# BikeNavigation.net
KiCad netlist of a schematic drawn in EAGLE
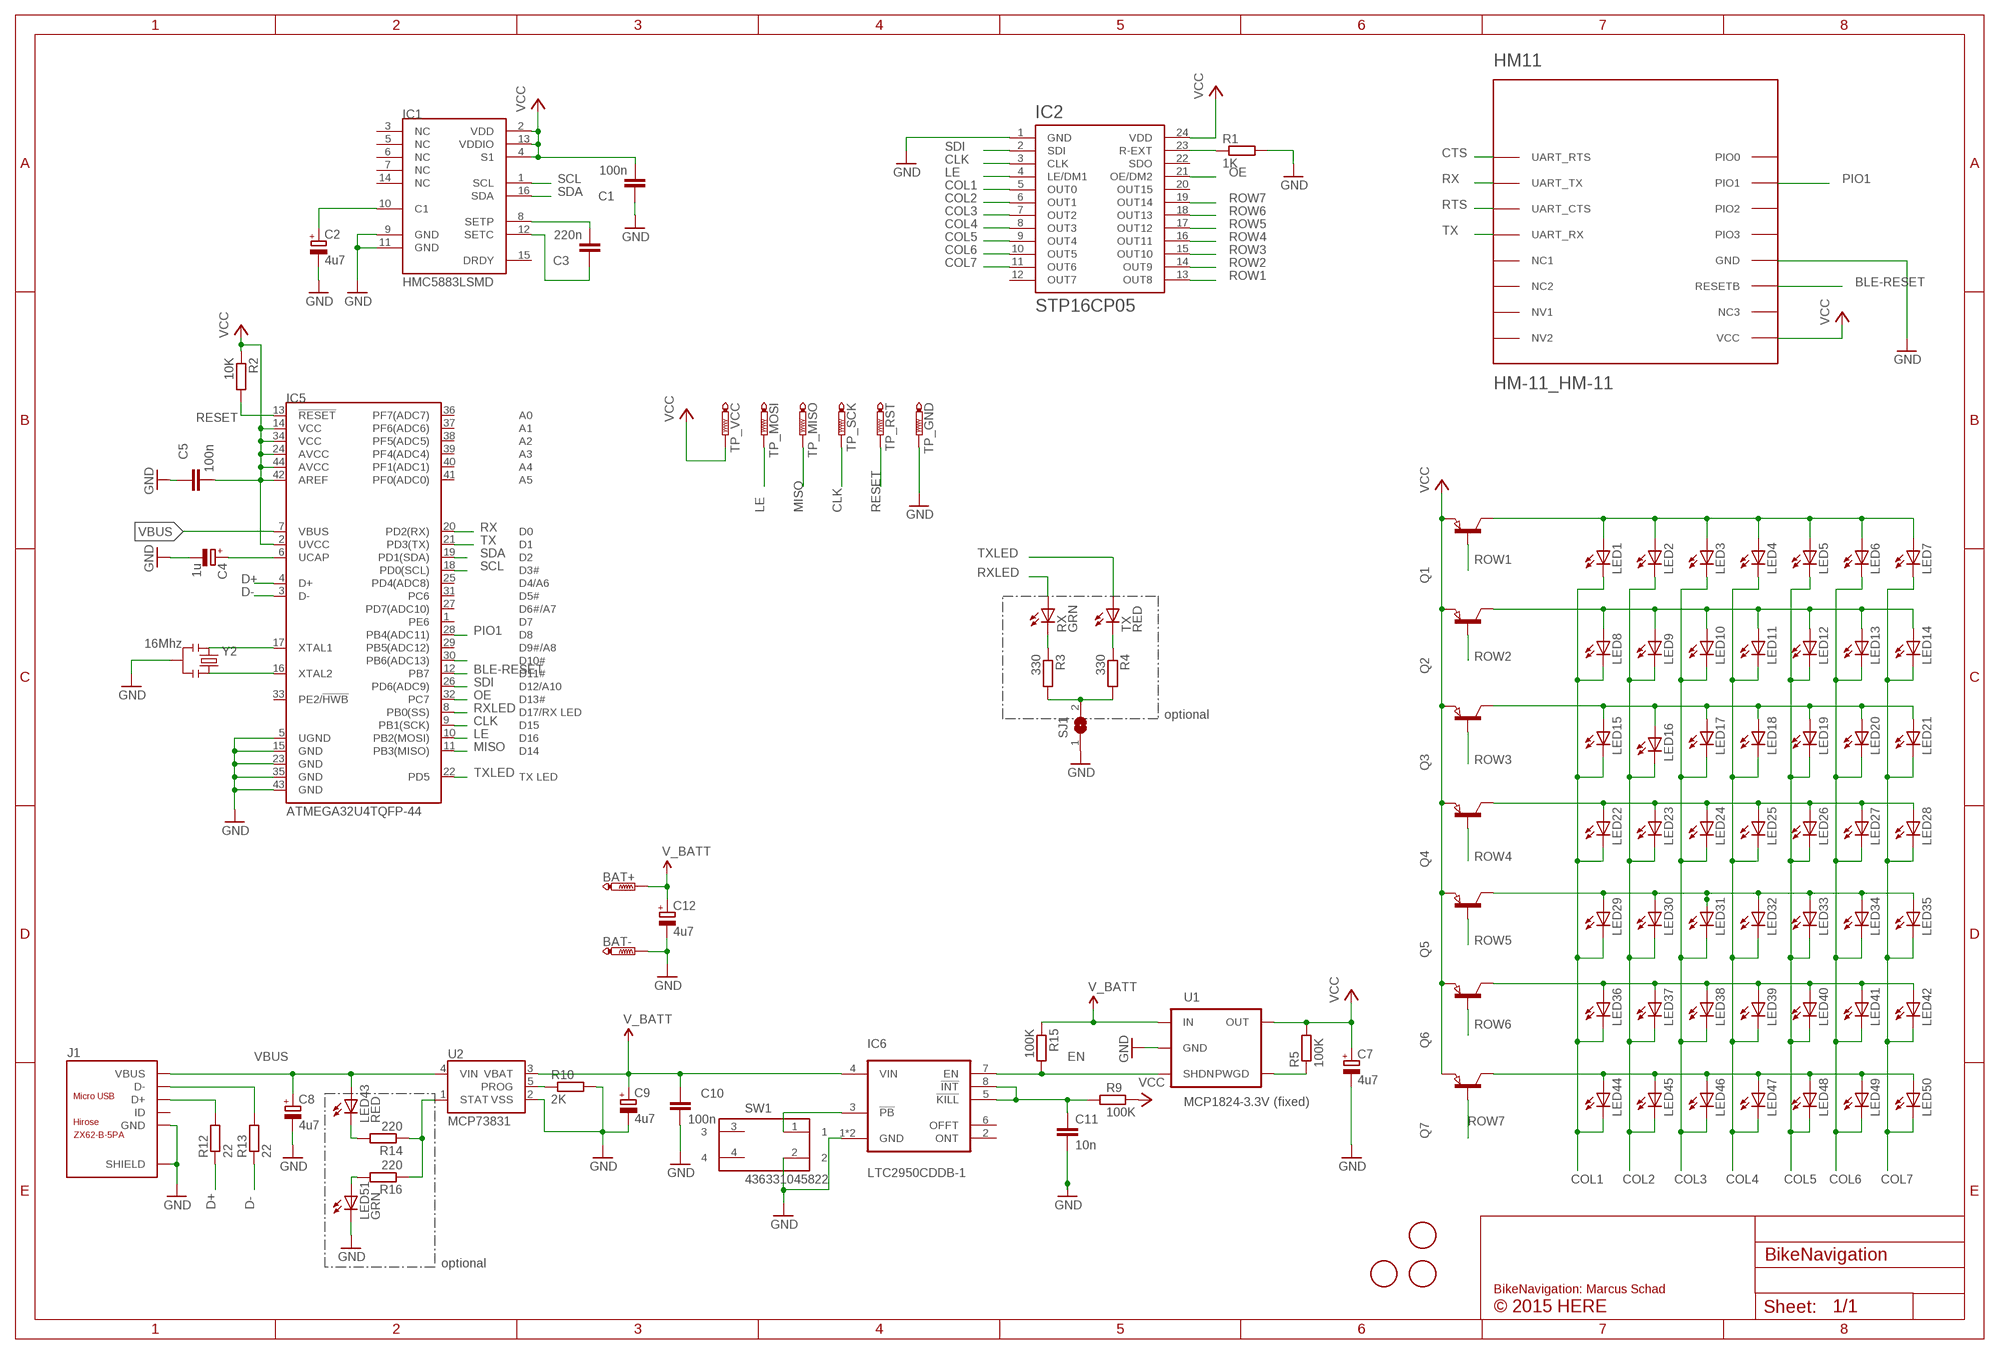
[diagram p0: schematic, sheet 1]

(export (version "E")
  (design (tool "Eeschema 10.0.6"))
  (components
    (comp (ref "BAT+")
      (value "PTR1TP20SQ")
      (footprint "eagle-import:TP20SQ")
      (libsource (lib "eagle-import") (part "PTR1TP20SQ"))
    )
    (comp (ref "BAT-")
      (value "PTR1TP20SQ")
      (footprint "eagle-import:TP20SQ")
      (libsource (lib "eagle-import") (part "PTR1TP20SQ"))
    )
    (comp (ref "C1")
      (value "100n")
      (footprint "eagle-import:C0402")
      (fields (field (name "PARTNO") "445-3445-1-ND"))
      (libsource (lib "eagle-import") (part "C-EUC0402"))
    )
    (comp (ref "C2")
      (value "4u7")
      (footprint "eagle-import:SMC_A")
      (libsource (lib "eagle-import") (part "CPOL-EUSMCA"))
    )
    (comp (ref "C3")
      (value "220n")
      (footprint "eagle-import:C0402")
      (fields (field (name "PARTNO") "445-3445-1-ND"))
      (libsource (lib "eagle-import") (part "C-EUC0402"))
    )
    (comp (ref "C4")
      (value "1u")
      (footprint "eagle-import:SMC_A")
      (libsource (lib "eagle-import") (part "CPOL-EUSMCA"))
    )
    (comp (ref "C5")
      (value "100n")
      (footprint "eagle-import:C0402")
      (fields (field (name "PARTNO") "445-3445-1-ND"))
      (libsource (lib "eagle-import") (part "C-EUC0402"))
    )
    (comp (ref "C7")
      (value "4u7")
      (footprint "eagle-import:SMC_A")
      (libsource (lib "eagle-import") (part "CPOL-EUSMCA"))
    )
    (comp (ref "C8")
      (value "4u7")
      (footprint "eagle-import:SMC_A")
      (libsource (lib "eagle-import") (part "CPOL-EUSMCA"))
    )
    (comp (ref "C9")
      (value "4u7")
      (footprint "eagle-import:SMC_A")
      (libsource (lib "eagle-import") (part "CPOL-EUSMCA"))
    )
    (comp (ref "C10")
      (value "100n")
      (footprint "eagle-import:C0402")
      (fields (field (name "PARTNO") "445-3445-1-ND"))
      (libsource (lib "eagle-import") (part "C-EUC0402"))
    )
    (comp (ref "C11")
      (value "10n")
      (footprint "eagle-import:C0402")
      (fields (field (name "PARTNO") "445-1260-1-ND"))
      (libsource (lib "eagle-import") (part "C-EUC0402"))
    )
    (comp (ref "C12")
      (value "4u7")
      (footprint "eagle-import:SMC_A")
      (libsource (lib "eagle-import") (part "CPOL-EUSMCA"))
    )
    (comp (ref "HM11")
      (value "HM-11_HM-11")
      (footprint "eagle-import:HM-11_HM-11")
      (libsource (lib "eagle-import") (part "HM-11_HM-11"))
    )
    (comp (ref "IC1")
      (value "HMC5883LSMD")
      (footprint "eagle-import:16LPCC")
      (libsource (lib "eagle-import") (part "HMC5883LSMD"))
    )
    (comp (ref "IC2")
      (value "STP16CP05")
      (footprint "eagle-import:TSSOP24")
      (libsource (lib "eagle-import") (part "STP16CP05"))
    )
    (comp (ref "IC5")
      (value "ATMEGA32U4TQFP-44")
      (footprint "eagle-import:TQFP44")
      (libsource (lib "eagle-import") (part "ATMEGA32U4TQFP-44"))
    )
    (comp (ref "IC6")
      (value "LTC2950CDDB-1")
      (footprint "eagle-import:DDB-8")
      (fields (field (name "PARTNO") "LTC2950IDDB-1#TRMPBFCT-ND"))
      (libsource (lib "eagle-import") (part "LTC2950-1DFN(3X2)"))
    )
    (comp (ref "J1")
      (value "MICRO-USB-SMD(ZX62-B-5PA)")
      (footprint "eagle-import:MICRO-USB5+6P-SMD-0.65-AB")
      (libsource (lib "eagle-import") (part "MICRO-USB-SMD(ZX62-B-5PA)"))
    )
    (comp (ref "LED1")
      (value "LEDCHIP-LED0603")
      (footprint "eagle-import:CHIP-LED0603")
      (libsource (lib "eagle-import") (part "LEDCHIP-LED0603"))
    )
    (comp (ref "LED2")
      (value "LEDCHIP-LED0603")
      (footprint "eagle-import:CHIP-LED0603")
      (libsource (lib "eagle-import") (part "LEDCHIP-LED0603"))
    )
    (comp (ref "LED3")
      (value "LEDCHIP-LED0603")
      (footprint "eagle-import:CHIP-LED0603")
      (libsource (lib "eagle-import") (part "LEDCHIP-LED0603"))
    )
    (comp (ref "LED4")
      (value "LEDCHIP-LED0603")
      (footprint "eagle-import:CHIP-LED0603")
      (libsource (lib "eagle-import") (part "LEDCHIP-LED0603"))
    )
    (comp (ref "LED5")
      (value "LEDCHIP-LED0603")
      (footprint "eagle-import:CHIP-LED0603")
      (libsource (lib "eagle-import") (part "LEDCHIP-LED0603"))
    )
    (comp (ref "LED6")
      (value "LEDCHIP-LED0603")
      (footprint "eagle-import:CHIP-LED0603")
      (libsource (lib "eagle-import") (part "LEDCHIP-LED0603"))
    )
    (comp (ref "LED7")
      (value "LEDCHIP-LED0603")
      (footprint "eagle-import:CHIP-LED0603")
      (libsource (lib "eagle-import") (part "LEDCHIP-LED0603"))
    )
    (comp (ref "LED8")
      (value "LEDCHIP-LED0603")
      (footprint "eagle-import:CHIP-LED0603")
      (libsource (lib "eagle-import") (part "LEDCHIP-LED0603"))
    )
    (comp (ref "LED9")
      (value "LEDCHIP-LED0603")
      (footprint "eagle-import:CHIP-LED0603")
      (libsource (lib "eagle-import") (part "LEDCHIP-LED0603"))
    )
    (comp (ref "LED10")
      (value "LEDCHIP-LED0603")
      (footprint "eagle-import:CHIP-LED0603")
      (libsource (lib "eagle-import") (part "LEDCHIP-LED0603"))
    )
    (comp (ref "LED11")
      (value "LEDCHIP-LED0603")
      (footprint "eagle-import:CHIP-LED0603")
      (libsource (lib "eagle-import") (part "LEDCHIP-LED0603"))
    )
    (comp (ref "LED12")
      (value "LEDCHIP-LED0603")
      (footprint "eagle-import:CHIP-LED0603")
      (libsource (lib "eagle-import") (part "LEDCHIP-LED0603"))
    )
    (comp (ref "LED13")
      (value "LEDCHIP-LED0603")
      (footprint "eagle-import:CHIP-LED0603")
      (libsource (lib "eagle-import") (part "LEDCHIP-LED0603"))
    )
    (comp (ref "LED14")
      (value "LEDCHIP-LED0603")
      (footprint "eagle-import:CHIP-LED0603")
      (libsource (lib "eagle-import") (part "LEDCHIP-LED0603"))
    )
    (comp (ref "LED15")
      (value "LEDCHIP-LED0603")
      (footprint "eagle-import:CHIP-LED0603")
      (libsource (lib "eagle-import") (part "LEDCHIP-LED0603"))
    )
    (comp (ref "LED16")
      (value "LEDCHIP-LED0603")
      (footprint "eagle-import:CHIP-LED0603")
      (libsource (lib "eagle-import") (part "LEDCHIP-LED0603"))
    )
    (comp (ref "LED17")
      (value "LEDCHIP-LED0603")
      (footprint "eagle-import:CHIP-LED0603")
      (libsource (lib "eagle-import") (part "LEDCHIP-LED0603"))
    )
    (comp (ref "LED18")
      (value "LEDCHIP-LED0603")
      (footprint "eagle-import:CHIP-LED0603")
      (libsource (lib "eagle-import") (part "LEDCHIP-LED0603"))
    )
    (comp (ref "LED19")
      (value "LEDCHIP-LED0603")
      (footprint "eagle-import:CHIP-LED0603")
      (libsource (lib "eagle-import") (part "LEDCHIP-LED0603"))
    )
    (comp (ref "LED20")
      (value "LEDCHIP-LED0603")
      (footprint "eagle-import:CHIP-LED0603")
      (libsource (lib "eagle-import") (part "LEDCHIP-LED0603"))
    )
    (comp (ref "LED21")
      (value "LEDCHIP-LED0603")
      (footprint "eagle-import:CHIP-LED0603")
      (libsource (lib "eagle-import") (part "LEDCHIP-LED0603"))
    )
    (comp (ref "LED22")
      (value "LEDCHIP-LED0603")
      (footprint "eagle-import:CHIP-LED0603")
      (libsource (lib "eagle-import") (part "LEDCHIP-LED0603"))
    )
    (comp (ref "LED23")
      (value "LEDCHIP-LED0603")
      (footprint "eagle-import:CHIP-LED0603")
      (libsource (lib "eagle-import") (part "LEDCHIP-LED0603"))
    )
    (comp (ref "LED24")
      (value "LEDCHIP-LED0603")
      (footprint "eagle-import:CHIP-LED0603")
      (libsource (lib "eagle-import") (part "LEDCHIP-LED0603"))
    )
    (comp (ref "LED25")
      (value "LEDCHIP-LED0603")
      (footprint "eagle-import:CHIP-LED0603")
      (libsource (lib "eagle-import") (part "LEDCHIP-LED0603"))
    )
    (comp (ref "LED26")
      (value "LEDCHIP-LED0603")
      (footprint "eagle-import:CHIP-LED0603")
      (libsource (lib "eagle-import") (part "LEDCHIP-LED0603"))
    )
    (comp (ref "LED27")
      (value "LEDCHIP-LED0603")
      (footprint "eagle-import:CHIP-LED0603")
      (libsource (lib "eagle-import") (part "LEDCHIP-LED0603"))
    )
    (comp (ref "LED28")
      (value "LEDCHIP-LED0603")
      (footprint "eagle-import:CHIP-LED0603")
      (libsource (lib "eagle-import") (part "LEDCHIP-LED0603"))
    )
    (comp (ref "LED29")
      (value "LEDCHIP-LED0603")
      (footprint "eagle-import:CHIP-LED0603")
      (libsource (lib "eagle-import") (part "LEDCHIP-LED0603"))
    )
    (comp (ref "LED30")
      (value "LEDCHIP-LED0603")
      (footprint "eagle-import:CHIP-LED0603")
      (libsource (lib "eagle-import") (part "LEDCHIP-LED0603"))
    )
    (comp (ref "LED31")
      (value "LEDCHIP-LED0603")
      (footprint "eagle-import:CHIP-LED0603")
      (libsource (lib "eagle-import") (part "LEDCHIP-LED0603"))
    )
    (comp (ref "LED32")
      (value "LEDCHIP-LED0603")
      (footprint "eagle-import:CHIP-LED0603")
      (libsource (lib "eagle-import") (part "LEDCHIP-LED0603"))
    )
    (comp (ref "LED33")
      (value "LEDCHIP-LED0603")
      (footprint "eagle-import:CHIP-LED0603")
      (libsource (lib "eagle-import") (part "LEDCHIP-LED0603"))
    )
    (comp (ref "LED34")
      (value "LEDCHIP-LED0603")
      (footprint "eagle-import:CHIP-LED0603")
      (libsource (lib "eagle-import") (part "LEDCHIP-LED0603"))
    )
    (comp (ref "LED35")
      (value "LEDCHIP-LED0603")
      (footprint "eagle-import:CHIP-LED0603")
      (libsource (lib "eagle-import") (part "LEDCHIP-LED0603"))
    )
    (comp (ref "LED36")
      (value "LEDCHIP-LED0603")
      (footprint "eagle-import:CHIP-LED0603")
      (libsource (lib "eagle-import") (part "LEDCHIP-LED0603"))
    )
    (comp (ref "LED37")
      (value "LEDCHIP-LED0603")
      (footprint "eagle-import:CHIP-LED0603")
      (libsource (lib "eagle-import") (part "LEDCHIP-LED0603"))
    )
    (comp (ref "LED38")
      (value "LEDCHIP-LED0603")
      (footprint "eagle-import:CHIP-LED0603")
      (libsource (lib "eagle-import") (part "LEDCHIP-LED0603"))
    )
    (comp (ref "LED39")
      (value "LEDCHIP-LED0603")
      (footprint "eagle-import:CHIP-LED0603")
      (libsource (lib "eagle-import") (part "LEDCHIP-LED0603"))
    )
    (comp (ref "LED40")
      (value "LEDCHIP-LED0603")
      (footprint "eagle-import:CHIP-LED0603")
      (libsource (lib "eagle-import") (part "LEDCHIP-LED0603"))
    )
    (comp (ref "LED41")
      (value "LEDCHIP-LED0603")
      (footprint "eagle-import:CHIP-LED0603")
      (libsource (lib "eagle-import") (part "LEDCHIP-LED0603"))
    )
    (comp (ref "LED42")
      (value "LEDCHIP-LED0603")
      (footprint "eagle-import:CHIP-LED0603")
      (libsource (lib "eagle-import") (part "LEDCHIP-LED0603"))
    )
    (comp (ref "LED43")
      (value "RED")
      (footprint "eagle-import:SML0805")
      (libsource (lib "eagle-import") (part "LEDSML0805"))
    )
    (comp (ref "LED44")
      (value "LEDCHIP-LED0603")
      (footprint "eagle-import:CHIP-LED0603")
      (libsource (lib "eagle-import") (part "LEDCHIP-LED0603"))
    )
    (comp (ref "LED45")
      (value "LEDCHIP-LED0603")
      (footprint "eagle-import:CHIP-LED0603")
      (libsource (lib "eagle-import") (part "LEDCHIP-LED0603"))
    )
    (comp (ref "LED46")
      (value "LEDCHIP-LED0603")
      (footprint "eagle-import:CHIP-LED0603")
      (libsource (lib "eagle-import") (part "LEDCHIP-LED0603"))
    )
    (comp (ref "LED47")
      (value "LEDCHIP-LED0603")
      (footprint "eagle-import:CHIP-LED0603")
      (libsource (lib "eagle-import") (part "LEDCHIP-LED0603"))
    )
    (comp (ref "LED48")
      (value "LEDCHIP-LED0603")
      (footprint "eagle-import:CHIP-LED0603")
      (libsource (lib "eagle-import") (part "LEDCHIP-LED0603"))
    )
    (comp (ref "LED49")
      (value "LEDCHIP-LED0603")
      (footprint "eagle-import:CHIP-LED0603")
      (libsource (lib "eagle-import") (part "LEDCHIP-LED0603"))
    )
    (comp (ref "LED50")
      (value "LEDCHIP-LED0603")
      (footprint "eagle-import:CHIP-LED0603")
      (libsource (lib "eagle-import") (part "LEDCHIP-LED0603"))
    )
    (comp (ref "LED51")
      (value "GRN")
      (footprint "eagle-import:SML0805")
      (libsource (lib "eagle-import") (part "LEDSML0805"))
    )
    (comp (ref "Q1")
      (value "PNP-TRANSISTOR_SOT23")
      (footprint "eagle-import:SOT23")
      (libsource (lib "eagle-import") (part "PNP-TRANSISTOR_SOT23"))
    )
    (comp (ref "Q2")
      (value "PNP-TRANSISTOR_SOT23")
      (footprint "eagle-import:SOT23")
      (libsource (lib "eagle-import") (part "PNP-TRANSISTOR_SOT23"))
    )
    (comp (ref "Q3")
      (value "PNP-TRANSISTOR_SOT23")
      (footprint "eagle-import:SOT23")
      (libsource (lib "eagle-import") (part "PNP-TRANSISTOR_SOT23"))
    )
    (comp (ref "Q4")
      (value "PNP-TRANSISTOR_SOT23")
      (footprint "eagle-import:SOT23")
      (libsource (lib "eagle-import") (part "PNP-TRANSISTOR_SOT23"))
    )
    (comp (ref "Q5")
      (value "PNP-TRANSISTOR_SOT23")
      (footprint "eagle-import:SOT23")
      (libsource (lib "eagle-import") (part "PNP-TRANSISTOR_SOT23"))
    )
    (comp (ref "Q6")
      (value "PNP-TRANSISTOR_SOT23")
      (footprint "eagle-import:SOT23")
      (libsource (lib "eagle-import") (part "PNP-TRANSISTOR_SOT23"))
    )
    (comp (ref "Q7")
      (value "PNP-TRANSISTOR_SOT23")
      (footprint "eagle-import:SOT23")
      (libsource (lib "eagle-import") (part "PNP-TRANSISTOR_SOT23"))
    )
    (comp (ref "R1")
      (value "1K")
      (footprint "eagle-import:R0402")
      (libsource (lib "eagle-import") (part "rcl_R-EU_R0402"))
    )
    (comp (ref "R2")
      (value "10K")
      (footprint "eagle-import:R0402")
      (libsource (lib "eagle-import") (part "rcl_R-EU_R0402"))
    )
    (comp (ref "R3")
      (value "330")
      (footprint "eagle-import:R0402")
      (libsource (lib "eagle-import") (part "rcl_R-EU_R0402"))
    )
    (comp (ref "R4")
      (value "330")
      (footprint "eagle-import:R0402")
      (libsource (lib "eagle-import") (part "rcl_R-EU_R0402"))
    )
    (comp (ref "R5")
      (value "100K")
      (footprint "eagle-import:R0402")
      (libsource (lib "eagle-import") (part "rcl_R-EU_R0402"))
    )
    (comp (ref "R9")
      (value "100K")
      (footprint "eagle-import:R0402")
      (fields (field (name "PARTNO") "P510KJCT-ND"))
      (libsource (lib "eagle-import") (part "R-EU_R0402"))
    )
    (comp (ref "R10")
      (value "2K")
      (footprint "eagle-import:R0402")
      (libsource (lib "eagle-import") (part "rcl_R-EU_R0402"))
    )
    (comp (ref "R12")
      (value "22")
      (footprint "eagle-import:R0402")
      (libsource (lib "eagle-import") (part "rcl_R-EU_R0402"))
    )
    (comp (ref "R13")
      (value "22")
      (footprint "eagle-import:R0402")
      (libsource (lib "eagle-import") (part "rcl_R-EU_R0402"))
    )
    (comp (ref "R14")
      (value "220")
      (footprint "eagle-import:R0402")
      (libsource (lib "eagle-import") (part "rcl_R-EU_R0402"))
    )
    (comp (ref "R15")
      (value "100K")
      (footprint "eagle-import:R0402")
      (fields (field (name "PARTNO") "P100KJCT-ND"))
      (libsource (lib "eagle-import") (part "R-EU_R0402"))
    )
    (comp (ref "R16")
      (value "220")
      (footprint "eagle-import:R0402")
      (libsource (lib "eagle-import") (part "rcl_R-EU_R0402"))
    )
    (comp (ref "RX")
      (value "GRN")
      (footprint "eagle-import:CHIP-LED0603")
      (libsource (lib "eagle-import") (part "LEDCHIP-LED0603"))
    )
    (comp (ref "SJ1") (value "SJ") (footprint "eagle-import:SJ") (libsource (lib "eagle-import") (part "SJ")))
    (comp (ref "SW1")
      (value "436331045822")
      (footprint "eagle-import:436331045822")
      (libsource (lib "eagle-import") (part "436331045822"))
    )
    (comp (ref "TP_GND")
      (value "PTR1TP20SQ")
      (footprint "eagle-import:TP20SQ")
      (libsource (lib "eagle-import") (part "PTR1TP20SQ"))
    )
    (comp (ref "TP_MISO")
      (value "PTR1TP20SQ")
      (footprint "eagle-import:TP20SQ")
      (libsource (lib "eagle-import") (part "PTR1TP20SQ"))
    )
    (comp (ref "TP_MOSI")
      (value "PTR1TP20SQ")
      (footprint "eagle-import:TP20SQ")
      (libsource (lib "eagle-import") (part "PTR1TP20SQ"))
    )
    (comp (ref "TP_RST")
      (value "PTR1TP20SQ")
      (footprint "eagle-import:TP20SQ")
      (libsource (lib "eagle-import") (part "PTR1TP20SQ"))
    )
    (comp (ref "TP_SCK")
      (value "PTR1TP20SQ")
      (footprint "eagle-import:TP20SQ")
      (libsource (lib "eagle-import") (part "PTR1TP20SQ"))
    )
    (comp (ref "TP_VCC")
      (value "PTR1TP20SQ")
      (footprint "eagle-import:TP20SQ")
      (libsource (lib "eagle-import") (part "PTR1TP20SQ"))
    )
    (comp (ref "TX")
      (value "RED")
      (footprint "eagle-import:CHIP-LED0603")
      (libsource (lib "eagle-import") (part "LEDCHIP-LED0603"))
    )
    (comp (ref "U$1")
      (value "FIDUCIAL")
      (footprint "eagle-import:FIDUCIAL_1MM")
      (libsource (lib "eagle-import") (part "FIDUCIAL"))
    )
    (comp (ref "U$2")
      (value "FIDUCIAL")
      (footprint "eagle-import:FIDUCIAL_1MM")
      (libsource (lib "eagle-import") (part "FIDUCIAL"))
    )
    (comp (ref "U$3")
      (value "FIDUCIAL")
      (footprint "eagle-import:FIDUCIAL_1MM")
      (libsource (lib "eagle-import") (part "FIDUCIAL"))
    )
    (comp (ref "U1")
      (value "MCP1824-3.3V (fixed)")
      (footprint "eagle-import:SOT23-5")
      (libsource (lib "eagle-import") (part "V_REG_LDOSMD"))
    )
    (comp (ref "U2")
      (value "MCP73831")
      (footprint "eagle-import:SOT23-5")
      (libsource (lib "eagle-import") (part "MCP73831"))
    )
    (comp (ref "Y2")
      (value "16Mhz")
      (footprint "eagle-import:RESONATOR-SMD")
      (libsource (lib "eagle-import") (part "RESONATORSMD"))
    )
  )
  (nets
    (net (code "1") (name "/BLE-RESET") (class "Default")
      (node (ref "HM11") (pin "RESETB") (pinfunction "RESETB_RESETB") (pintype "bidirectional"))
      (node (ref "IC5") (pin "12") (pinfunction "PB7_12") (pintype "bidirectional"))
    )
    (net (code "2") (name "/CLK") (class "Default")
      (node (ref "IC2") (pin "3") (pinfunction "CLK_3") (pintype "bidirectional"))
      (node (ref "IC5") (pin "9") (pinfunction "PB1(SCK)_9") (pintype "bidirectional"))
      (node (ref "TP_SCK") (pin "TP") (pinfunction "TP_TP") (pintype "input"))
    )
    (net (code "3") (name "/COL1") (class "Default")
      (node (ref "IC2") (pin "5") (pinfunction "OUT0_5") (pintype "bidirectional"))
      (node (ref "LED1") (pin "C") (pinfunction "C_C") (pintype "passive"))
      (node (ref "LED15") (pin "C") (pinfunction "C_C") (pintype "passive"))
      (node (ref "LED22") (pin "C") (pinfunction "C_C") (pintype "passive"))
      (node (ref "LED29") (pin "C") (pinfunction "C_C") (pintype "passive"))
      (node (ref "LED36") (pin "C") (pinfunction "C_C") (pintype "passive"))
      (node (ref "LED44") (pin "C") (pinfunction "C_C") (pintype "passive"))
      (node (ref "LED8") (pin "C") (pinfunction "C_C") (pintype "passive"))
    )
    (net (code "4") (name "/COL2") (class "Default")
      (node (ref "IC2") (pin "6") (pinfunction "OUT1_6") (pintype "bidirectional"))
      (node (ref "LED16") (pin "C") (pinfunction "C_C") (pintype "passive"))
      (node (ref "LED2") (pin "C") (pinfunction "C_C") (pintype "passive"))
      (node (ref "LED23") (pin "C") (pinfunction "C_C") (pintype "passive"))
      (node (ref "LED30") (pin "C") (pinfunction "C_C") (pintype "passive"))
      (node (ref "LED37") (pin "C") (pinfunction "C_C") (pintype "passive"))
      (node (ref "LED45") (pin "C") (pinfunction "C_C") (pintype "passive"))
      (node (ref "LED9") (pin "C") (pinfunction "C_C") (pintype "passive"))
    )
    (net (code "5") (name "/COL3") (class "Default")
      (node (ref "IC2") (pin "7") (pinfunction "OUT2_7") (pintype "bidirectional"))
      (node (ref "LED10") (pin "C") (pinfunction "C_C") (pintype "passive"))
      (node (ref "LED17") (pin "C") (pinfunction "C_C") (pintype "passive"))
      (node (ref "LED24") (pin "C") (pinfunction "C_C") (pintype "passive"))
      (node (ref "LED3") (pin "C") (pinfunction "C_C") (pintype "passive"))
      (node (ref "LED31") (pin "C") (pinfunction "C_C") (pintype "passive"))
      (node (ref "LED38") (pin "C") (pinfunction "C_C") (pintype "passive"))
      (node (ref "LED46") (pin "C") (pinfunction "C_C") (pintype "passive"))
    )
    (net (code "6") (name "/COL4") (class "Default")
      (node (ref "IC2") (pin "8") (pinfunction "OUT3_8") (pintype "bidirectional"))
      (node (ref "LED11") (pin "C") (pinfunction "C_C") (pintype "passive"))
      (node (ref "LED18") (pin "C") (pinfunction "C_C") (pintype "passive"))
      (node (ref "LED25") (pin "C") (pinfunction "C_C") (pintype "passive"))
      (node (ref "LED32") (pin "C") (pinfunction "C_C") (pintype "passive"))
      (node (ref "LED39") (pin "C") (pinfunction "C_C") (pintype "passive"))
      (node (ref "LED4") (pin "C") (pinfunction "C_C") (pintype "passive"))
      (node (ref "LED47") (pin "C") (pinfunction "C_C") (pintype "passive"))
    )
    (net (code "7") (name "/COL5") (class "Default")
      (node (ref "IC2") (pin "9") (pinfunction "OUT4_9") (pintype "bidirectional"))
      (node (ref "LED12") (pin "C") (pinfunction "C_C") (pintype "passive"))
      (node (ref "LED19") (pin "C") (pinfunction "C_C") (pintype "passive"))
      (node (ref "LED26") (pin "C") (pinfunction "C_C") (pintype "passive"))
      (node (ref "LED33") (pin "C") (pinfunction "C_C") (pintype "passive"))
      (node (ref "LED40") (pin "C") (pinfunction "C_C") (pintype "passive"))
      (node (ref "LED48") (pin "C") (pinfunction "C_C") (pintype "passive"))
      (node (ref "LED5") (pin "C") (pinfunction "C_C") (pintype "passive"))
    )
    (net (code "8") (name "/COL6") (class "Default")
      (node (ref "IC2") (pin "10") (pinfunction "OUT5_10") (pintype "bidirectional"))
      (node (ref "LED13") (pin "C") (pinfunction "C_C") (pintype "passive"))
      (node (ref "LED20") (pin "C") (pinfunction "C_C") (pintype "passive"))
      (node (ref "LED27") (pin "C") (pinfunction "C_C") (pintype "passive"))
      (node (ref "LED34") (pin "C") (pinfunction "C_C") (pintype "passive"))
      (node (ref "LED41") (pin "C") (pinfunction "C_C") (pintype "passive"))
      (node (ref "LED49") (pin "C") (pinfunction "C_C") (pintype "passive"))
      (node (ref "LED6") (pin "C") (pinfunction "C_C") (pintype "passive"))
    )
    (net (code "9") (name "/COL7") (class "Default")
      (node (ref "IC2") (pin "11") (pinfunction "OUT6_11") (pintype "bidirectional"))
      (node (ref "LED14") (pin "C") (pinfunction "C_C") (pintype "passive"))
      (node (ref "LED21") (pin "C") (pinfunction "C_C") (pintype "passive"))
      (node (ref "LED28") (pin "C") (pinfunction "C_C") (pintype "passive"))
      (node (ref "LED35") (pin "C") (pinfunction "C_C") (pintype "passive"))
      (node (ref "LED42") (pin "C") (pinfunction "C_C") (pintype "passive"))
      (node (ref "LED50") (pin "C") (pinfunction "C_C") (pintype "passive"))
      (node (ref "LED7") (pin "C") (pinfunction "C_C") (pintype "passive"))
    )
    (net (code "10") (name "/CTS") (class "Default")
      (node (ref "HM11") (pin "UART_RTS") (pinfunction "UART_RTS_UART_RTS") (pintype "bidirectional"))
    )
    (net (code "11") (name "/D+") (class "Default")
      (node (ref "IC5") (pin "4") (pinfunction "D+_4") (pintype "bidirectional"))
      (node (ref "R12") (pin "1") (pinfunction "1_1") (pintype "passive"))
    )
    (net (code "12") (name "/D-") (class "Default")
      (node (ref "IC5") (pin "3") (pinfunction "D-_3") (pintype "bidirectional"))
      (node (ref "R13") (pin "1") (pinfunction "1_1") (pintype "passive"))
    )
    (net (code "13") (name "/EN") (class "Default")
      (node (ref "IC6") (pin "7") (pinfunction "EN_7") (pintype "output"))
      (node (ref "R15") (pin "2") (pinfunction "2_2") (pintype "passive"))
      (node (ref "U1") (pin "3") (pinfunction "SHDN_3") (pintype "input"))
    )
    (net (code "14") (name "/LE") (class "Default")
      (node (ref "IC2") (pin "4") (pinfunction "LE/DM1_4") (pintype "bidirectional"))
      (node (ref "IC5") (pin "10") (pinfunction "PB2(MOSI)_10") (pintype "bidirectional"))
      (node (ref "TP_MOSI") (pin "TP") (pinfunction "TP_TP") (pintype "input"))
    )
    (net (code "15") (name "/MISO") (class "Default")
      (node (ref "IC5") (pin "11") (pinfunction "PB3(MISO)_11") (pintype "bidirectional"))
      (node (ref "TP_MISO") (pin "TP") (pinfunction "TP_TP") (pintype "input"))
    )
    (net (code "16") (name "/OE") (class "Default")
      (node (ref "IC2") (pin "21") (pinfunction "OE/DM2_21") (pintype "bidirectional"))
      (node (ref "IC5") (pin "32") (pinfunction "PC7_32") (pintype "bidirectional"))
    )
    (net (code "17") (name "/PIO1") (class "Default")
      (node (ref "HM11") (pin "PIO1") (pinfunction "PIO1_PIO1") (pintype "bidirectional"))
      (node (ref "IC5") (pin "28") (pinfunction "PB4(ADC11)_28") (pintype "bidirectional"))
    )
    (net (code "18") (name "/RESET") (class "Default")
      (node (ref "IC5") (pin "13") (pinfunction "~{RESET}_13") (pintype "bidirectional"))
      (node (ref "R2") (pin "2") (pinfunction "2_2") (pintype "passive"))
      (node (ref "TP_RST") (pin "TP") (pinfunction "TP_TP") (pintype "input"))
    )
    (net (code "19") (name "/ROW1") (class "Default")
      (node (ref "IC2") (pin "13") (pinfunction "OUT8_13") (pintype "bidirectional"))
      (node (ref "Q1") (pin "1") (pinfunction "B_1") (pintype "passive"))
    )
    (net (code "20") (name "/ROW2") (class "Default")
      (node (ref "IC2") (pin "14") (pinfunction "OUT9_14") (pintype "bidirectional"))
      (node (ref "Q2") (pin "1") (pinfunction "B_1") (pintype "passive"))
    )
    (net (code "21") (name "/ROW3") (class "Default")
      (node (ref "IC2") (pin "15") (pinfunction "OUT10_15") (pintype "bidirectional"))
      (node (ref "Q3") (pin "1") (pinfunction "B_1") (pintype "passive"))
    )
    (net (code "22") (name "/ROW4") (class "Default")
      (node (ref "IC2") (pin "16") (pinfunction "OUT11_16") (pintype "bidirectional"))
      (node (ref "Q4") (pin "1") (pinfunction "B_1") (pintype "passive"))
    )
    (net (code "23") (name "/ROW5") (class "Default")
      (node (ref "IC2") (pin "17") (pinfunction "OUT12_17") (pintype "bidirectional"))
      (node (ref "Q5") (pin "1") (pinfunction "B_1") (pintype "passive"))
    )
    (net (code "24") (name "/ROW6") (class "Default")
      (node (ref "IC2") (pin "18") (pinfunction "OUT13_18") (pintype "bidirectional"))
      (node (ref "Q6") (pin "1") (pinfunction "B_1") (pintype "passive"))
    )
    (net (code "25") (name "/ROW7") (class "Default")
      (node (ref "IC2") (pin "19") (pinfunction "OUT14_19") (pintype "bidirectional"))
      (node (ref "Q7") (pin "1") (pinfunction "B_1") (pintype "passive"))
    )
    (net (code "26") (name "/RTS") (class "Default")
      (node (ref "HM11") (pin "UART_CTS") (pinfunction "UART_CTS_UART_CTS") (pintype "bidirectional"))
    )
    (net (code "27") (name "/RX") (class "Default")
      (node (ref "HM11") (pin "UART_TX") (pinfunction "UART_TX_UART_TX") (pintype "bidirectional"))
      (node (ref "IC5") (pin "20") (pinfunction "PD2(RX)_20") (pintype "bidirectional"))
    )
    (net (code "28") (name "/RXLED") (class "Default")
      (node (ref "IC5") (pin "8") (pinfunction "PB0(SS)_8") (pintype "bidirectional"))
      (node (ref "RX") (pin "A") (pinfunction "A_A") (pintype "passive"))
    )
    (net (code "29") (name "/SCL") (class "Default")
      (node (ref "IC1") (pin "1") (pinfunction "SCL_1") (pintype "bidirectional"))
      (node (ref "IC5") (pin "18") (pinfunction "PD0(SCL)_18") (pintype "bidirectional"))
    )
    (net (code "30") (name "/SDA") (class "Default")
      (node (ref "IC1") (pin "16") (pinfunction "SDA_16") (pintype "bidirectional"))
      (node (ref "IC5") (pin "19") (pinfunction "PD1(SDA)_19") (pintype "bidirectional"))
    )
    (net (code "31") (name "/SDI") (class "Default")
      (node (ref "IC2") (pin "2") (pinfunction "SDI_2") (pintype "bidirectional"))
      (node (ref "IC5") (pin "26") (pinfunction "PD6(ADC9)_26") (pintype "bidirectional"))
    )
    (net (code "32") (name "/TX") (class "Default")
      (node (ref "HM11") (pin "UART_RX") (pinfunction "UART_RX_UART_RX") (pintype "bidirectional"))
      (node (ref "IC5") (pin "21") (pinfunction "PD3(TX)_21") (pintype "bidirectional"))
    )
    (net (code "33") (name "/TXLED") (class "Default")
      (node (ref "IC5") (pin "22") (pinfunction "PD5_22") (pintype "bidirectional"))
      (node (ref "TX") (pin "A") (pinfunction "A_A") (pintype "passive"))
    )
    (net (code "34") (name "GND") (class "Default")
      (node (ref "BAT-") (pin "TP") (pinfunction "TP_TP") (pintype "input"))
      (node (ref "C1") (pin "1") (pinfunction "1_1") (pintype "passive"))
      (node (ref "C10") (pin "2") (pinfunction "2_2") (pintype "passive"))
      (node (ref "C11") (pin "2") (pinfunction "2_2") (pintype "passive"))
      (node (ref "C12") (pin "-") (pinfunction "-_-") (pintype "passive"))
      (node (ref "C2") (pin "-") (pinfunction "-_-") (pintype "passive"))
      (node (ref "C4") (pin "-") (pinfunction "-_-") (pintype "passive"))
      (node (ref "C5") (pin "1") (pinfunction "1_1") (pintype "passive"))
      (node (ref "C7") (pin "-") (pinfunction "-_-") (pintype "passive"))
      (node (ref "C8") (pin "-") (pinfunction "-_-") (pintype "passive"))
      (node (ref "C9") (pin "-") (pinfunction "-_-") (pintype "passive"))
      (node (ref "HM11") (pin "GND") (pinfunction "GND_GND") (pintype "bidirectional"))
      (node (ref "IC1") (pin "11") (pinfunction "GND_11") (pintype "bidirectional"))
      (node (ref "IC1") (pin "9") (pinfunction "GND_9") (pintype "bidirectional"))
      (node (ref "IC2") (pin "1") (pinfunction "GND_1") (pintype "bidirectional"))
      (node (ref "IC5") (pin "15") (pinfunction "GND_15") (pintype "bidirectional"))
      (node (ref "IC5") (pin "23") (pinfunction "GND_23") (pintype "bidirectional"))
      (node (ref "IC5") (pin "35") (pinfunction "GND_35") (pintype "bidirectional"))
      (node (ref "IC5") (pin "43") (pinfunction "GND_43") (pintype "bidirectional"))
      (node (ref "IC5") (pin "5") (pinfunction "UGND_5") (pintype "bidirectional"))
      (node (ref "IC6") (pin "1") (pinfunction "GND_1") (pintype "power_in"))
      (node (ref "IC6") (pin "TPAD") (pinfunction "GND_TPAD") (pintype "power_in"))
      (node (ref "J1") (pin "5") (pinfunction "GND_5") (pintype "power_in"))
      (node (ref "J1") (pin "P1") (pinfunction "SHIELD_P1") (pintype "power_in"))
      (node (ref "J1") (pin "P2") (pinfunction "SHIELD_P2") (pintype "power_in"))
      (node (ref "J1") (pin "P3") (pinfunction "SHIELD_P3") (pintype "power_in"))
      (node (ref "J1") (pin "P4") (pinfunction "SHIELD_P4") (pintype "power_in"))
      (node (ref "J1") (pin "P5") (pinfunction "SHIELD_P5") (pintype "power_in"))
      (node (ref "J1") (pin "P6") (pinfunction "SHIELD_P6") (pintype "power_in"))
      (node (ref "LED51") (pin "C") (pinfunction "C_C") (pintype "passive"))
      (node (ref "R1") (pin "2") (pinfunction "2_2") (pintype "passive"))
      (node (ref "R10") (pin "2") (pinfunction "2_2") (pintype "passive"))
      (node (ref "SJ1") (pin "1") (pinfunction "1_1") (pintype "passive"))
      (node (ref "SW1") (pin "2") (pinfunction "2_2") (pintype "bidirectional"))
      (node (ref "TP_GND") (pin "TP") (pinfunction "TP_TP") (pintype "input"))
      (node (ref "U1") (pin "2") (pinfunction "GND_2") (pintype "input"))
      (node (ref "U2") (pin "2") (pinfunction "VSS_2") (pintype "power_in"))
      (node (ref "Y2") (pin "2") (pinfunction "2_2") (pintype "passive"))
    )
    (net (code "35") (name "Net-(IC1-C1)") (class "Default")
      (node (ref "C2") (pin "+") (pinfunction "+_+") (pintype "passive"))
      (node (ref "IC1") (pin "10") (pinfunction "C1_10") (pintype "bidirectional"))
    )
    (net (code "36") (name "Net-(IC1-SETC)") (class "Default")
      (node (ref "C3") (pin "1") (pinfunction "1_1") (pintype "passive"))
      (node (ref "IC1") (pin "12") (pinfunction "SETC_12") (pintype "bidirectional"))
    )
    (net (code "37") (name "Net-(IC1-SETP)") (class "Default")
      (node (ref "C3") (pin "2") (pinfunction "2_2") (pintype "passive"))
      (node (ref "IC1") (pin "8") (pinfunction "SETP_8") (pintype "bidirectional"))
    )
    (net (code "38") (name "Net-(IC2-R-EXT)") (class "Default")
      (node (ref "IC2") (pin "23") (pinfunction "R-EXT_23") (pintype "bidirectional"))
      (node (ref "R1") (pin "1") (pinfunction "1_1") (pintype "passive"))
    )
    (net (code "39") (name "Net-(IC5-UCAP)") (class "Default")
      (node (ref "C4") (pin "+") (pinfunction "+_+") (pintype "passive"))
      (node (ref "IC5") (pin "6") (pinfunction "UCAP_6") (pintype "bidirectional"))
    )
    (net (code "40") (name "Net-(IC5-XTAL1)") (class "Default")
      (node (ref "IC5") (pin "17") (pinfunction "XTAL1_17") (pintype "bidirectional"))
      (node (ref "Y2") (pin "1") (pinfunction "1_1") (pintype "passive"))
    )
    (net (code "41") (name "Net-(IC5-XTAL2)") (class "Default")
      (node (ref "IC5") (pin "16") (pinfunction "XTAL2_16") (pintype "bidirectional"))
      (node (ref "Y2") (pin "3") (pinfunction "3_3") (pintype "passive"))
    )
    (net (code "42") (name "Net-(IC6-~{INT})") (class "Default")
      (node (ref "C11") (pin "1") (pinfunction "1_1") (pintype "passive"))
      (node (ref "IC6") (pin "5") (pinfunction "~{KILL}_5") (pintype "input"))
      (node (ref "IC6") (pin "8") (pinfunction "~{INT}_8") (pintype "output"))
      (node (ref "R9") (pin "1") (pinfunction "1_1") (pintype "passive"))
    )
    (net (code "43") (name "Net-(IC6-~{PB})") (class "Default")
      (node (ref "IC6") (pin "3") (pinfunction "~{PB}_3") (pintype "input"))
      (node (ref "SW1") (pin "1") (pinfunction "1_1") (pintype "bidirectional"))
    )
    (net (code "44") (name "Net-(J1-D+)") (class "Default")
      (node (ref "J1") (pin "3") (pinfunction "D+_3") (pintype "bidirectional"))
      (node (ref "R12") (pin "2") (pinfunction "2_2") (pintype "passive"))
    )
    (net (code "45") (name "Net-(J1-D-)") (class "Default")
      (node (ref "J1") (pin "2") (pinfunction "D-_2") (pintype "bidirectional"))
      (node (ref "R13") (pin "2") (pinfunction "2_2") (pintype "passive"))
    )
    (net (code "46") (name "Net-(LED43-PadC)") (class "Default")
      (node (ref "LED43") (pin "C") (pinfunction "C_C") (pintype "passive"))
      (node (ref "R14") (pin "2") (pinfunction "2_2") (pintype "passive"))
    )
    (net (code "47") (name "Net-(LED51-PadA)") (class "Default")
      (node (ref "LED51") (pin "A") (pinfunction "A_A") (pintype "passive"))
      (node (ref "R16") (pin "2") (pinfunction "2_2") (pintype "passive"))
    )
    (net (code "48") (name "Net-(Q1-C)") (class "Default")
      (node (ref "LED1") (pin "A") (pinfunction "A_A") (pintype "passive"))
      (node (ref "LED2") (pin "A") (pinfunction "A_A") (pintype "passive"))
      (node (ref "LED3") (pin "A") (pinfunction "A_A") (pintype "passive"))
      (node (ref "LED4") (pin "A") (pinfunction "A_A") (pintype "passive"))
      (node (ref "LED5") (pin "A") (pinfunction "A_A") (pintype "passive"))
      (node (ref "LED6") (pin "A") (pinfunction "A_A") (pintype "passive"))
      (node (ref "LED7") (pin "A") (pinfunction "A_A") (pintype "passive"))
      (node (ref "Q1") (pin "3") (pinfunction "C_3") (pintype "passive"))
    )
    (net (code "49") (name "Net-(Q2-C)") (class "Default")
      (node (ref "LED10") (pin "A") (pinfunction "A_A") (pintype "passive"))
      (node (ref "LED11") (pin "A") (pinfunction "A_A") (pintype "passive"))
      (node (ref "LED12") (pin "A") (pinfunction "A_A") (pintype "passive"))
      (node (ref "LED13") (pin "A") (pinfunction "A_A") (pintype "passive"))
      (node (ref "LED14") (pin "A") (pinfunction "A_A") (pintype "passive"))
      (node (ref "LED8") (pin "A") (pinfunction "A_A") (pintype "passive"))
      (node (ref "LED9") (pin "A") (pinfunction "A_A") (pintype "passive"))
      (node (ref "Q2") (pin "3") (pinfunction "C_3") (pintype "passive"))
    )
    (net (code "50") (name "Net-(Q3-C)") (class "Default")
      (node (ref "LED15") (pin "A") (pinfunction "A_A") (pintype "passive"))
      (node (ref "LED16") (pin "A") (pinfunction "A_A") (pintype "passive"))
      (node (ref "LED17") (pin "A") (pinfunction "A_A") (pintype "passive"))
      (node (ref "LED18") (pin "A") (pinfunction "A_A") (pintype "passive"))
      (node (ref "LED19") (pin "A") (pinfunction "A_A") (pintype "passive"))
      (node (ref "LED20") (pin "A") (pinfunction "A_A") (pintype "passive"))
      (node (ref "LED21") (pin "A") (pinfunction "A_A") (pintype "passive"))
      (node (ref "Q3") (pin "3") (pinfunction "C_3") (pintype "passive"))
    )
    (net (code "51") (name "Net-(Q4-C)") (class "Default")
      (node (ref "LED22") (pin "A") (pinfunction "A_A") (pintype "passive"))
      (node (ref "LED23") (pin "A") (pinfunction "A_A") (pintype "passive"))
      (node (ref "LED24") (pin "A") (pinfunction "A_A") (pintype "passive"))
      (node (ref "LED25") (pin "A") (pinfunction "A_A") (pintype "passive"))
      (node (ref "LED26") (pin "A") (pinfunction "A_A") (pintype "passive"))
      (node (ref "LED27") (pin "A") (pinfunction "A_A") (pintype "passive"))
      (node (ref "LED28") (pin "A") (pinfunction "A_A") (pintype "passive"))
      (node (ref "Q4") (pin "3") (pinfunction "C_3") (pintype "passive"))
    )
    (net (code "52") (name "Net-(Q5-C)") (class "Default")
      (node (ref "LED29") (pin "A") (pinfunction "A_A") (pintype "passive"))
      (node (ref "LED30") (pin "A") (pinfunction "A_A") (pintype "passive"))
      (node (ref "LED31") (pin "A") (pinfunction "A_A") (pintype "passive"))
      (node (ref "LED32") (pin "A") (pinfunction "A_A") (pintype "passive"))
      (node (ref "LED33") (pin "A") (pinfunction "A_A") (pintype "passive"))
      (node (ref "LED34") (pin "A") (pinfunction "A_A") (pintype "passive"))
      (node (ref "LED35") (pin "A") (pinfunction "A_A") (pintype "passive"))
      (node (ref "Q5") (pin "3") (pinfunction "C_3") (pintype "passive"))
    )
    (net (code "53") (name "Net-(Q6-C)") (class "Default")
      (node (ref "LED36") (pin "A") (pinfunction "A_A") (pintype "passive"))
      (node (ref "LED37") (pin "A") (pinfunction "A_A") (pintype "passive"))
      (node (ref "LED38") (pin "A") (pinfunction "A_A") (pintype "passive"))
      (node (ref "LED39") (pin "A") (pinfunction "A_A") (pintype "passive"))
      (node (ref "LED40") (pin "A") (pinfunction "A_A") (pintype "passive"))
      (node (ref "LED41") (pin "A") (pinfunction "A_A") (pintype "passive"))
      (node (ref "LED42") (pin "A") (pinfunction "A_A") (pintype "passive"))
      (node (ref "Q6") (pin "3") (pinfunction "C_3") (pintype "passive"))
    )
    (net (code "54") (name "Net-(Q7-C)") (class "Default")
      (node (ref "LED44") (pin "A") (pinfunction "A_A") (pintype "passive"))
      (node (ref "LED45") (pin "A") (pinfunction "A_A") (pintype "passive"))
      (node (ref "LED46") (pin "A") (pinfunction "A_A") (pintype "passive"))
      (node (ref "LED47") (pin "A") (pinfunction "A_A") (pintype "passive"))
      (node (ref "LED48") (pin "A") (pinfunction "A_A") (pintype "passive"))
      (node (ref "LED49") (pin "A") (pinfunction "A_A") (pintype "passive"))
      (node (ref "LED50") (pin "A") (pinfunction "A_A") (pintype "passive"))
      (node (ref "Q7") (pin "3") (pinfunction "C_3") (pintype "passive"))
    )
    (net (code "55") (name "Net-(R3-Pad1)") (class "Default")
      (node (ref "R3") (pin "1") (pinfunction "1_1") (pintype "passive"))
      (node (ref "RX") (pin "C") (pinfunction "C_C") (pintype "passive"))
    )
    (net (code "56") (name "Net-(R3-Pad2)") (class "Default")
      (node (ref "R3") (pin "2") (pinfunction "2_2") (pintype "passive"))
      (node (ref "R4") (pin "2") (pinfunction "2_2") (pintype "passive"))
      (node (ref "SJ1") (pin "2") (pinfunction "2_2") (pintype "passive"))
    )
    (net (code "57") (name "Net-(R4-Pad1)") (class "Default")
      (node (ref "R4") (pin "1") (pinfunction "1_1") (pintype "passive"))
      (node (ref "TX") (pin "C") (pinfunction "C_C") (pintype "passive"))
    )
    (net (code "58") (name "Net-(U1-PWGD)") (class "Default")
      (node (ref "R5") (pin "1") (pinfunction "1_1") (pintype "passive"))
      (node (ref "U1") (pin "4") (pinfunction "PWGD_4") (pintype "input"))
    )
    (net (code "59") (name "Net-(U2-PROG)") (class "Default")
      (node (ref "R10") (pin "1") (pinfunction "1_1") (pintype "passive"))
      (node (ref "U2") (pin "5") (pinfunction "PROG_5") (pintype "input"))
    )
    (net (code "60") (name "Net-(U2-STAT)") (class "Default")
      (node (ref "R14") (pin "1") (pinfunction "1_1") (pintype "passive"))
      (node (ref "R16") (pin "1") (pinfunction "1_1") (pintype "passive"))
      (node (ref "U2") (pin "1") (pinfunction "STAT_1") (pintype "output"))
    )
    (net (code "61") (name "VBUS") (class "Default")
      (node (ref "C8") (pin "+") (pinfunction "+_+") (pintype "passive"))
      (node (ref "IC5") (pin "7") (pinfunction "VBUS_7") (pintype "bidirectional"))
      (node (ref "J1") (pin "1") (pinfunction "VBUS_1") (pintype "power_in"))
      (node (ref "LED43") (pin "A") (pinfunction "A_A") (pintype "passive"))
      (node (ref "U2") (pin "4") (pinfunction "VIN_4") (pintype "power_in"))
    )
    (net (code "62") (name "VCC") (class "Default")
      (node (ref "C1") (pin "2") (pinfunction "2_2") (pintype "passive"))
      (node (ref "C5") (pin "2") (pinfunction "2_2") (pintype "passive"))
      (node (ref "C7") (pin "+") (pinfunction "+_+") (pintype "passive"))
      (node (ref "HM11") (pin "VCC") (pinfunction "VCC_VCC") (pintype "bidirectional"))
      (node (ref "IC1") (pin "13") (pinfunction "VDDIO_13") (pintype "bidirectional"))
      (node (ref "IC1") (pin "2") (pinfunction "VDD_2") (pintype "bidirectional"))
      (node (ref "IC1") (pin "4") (pinfunction "S1_4") (pintype "bidirectional"))
      (node (ref "IC2") (pin "24") (pinfunction "VDD_24") (pintype "bidirectional"))
      (node (ref "IC5") (pin "14") (pinfunction "VCC_14") (pintype "bidirectional"))
      (node (ref "IC5") (pin "2") (pinfunction "UVCC_2") (pintype "bidirectional"))
      (node (ref "IC5") (pin "24") (pinfunction "AVCC_24") (pintype "bidirectional"))
      (node (ref "IC5") (pin "34") (pinfunction "VCC_34") (pintype "bidirectional"))
      (node (ref "IC5") (pin "42") (pinfunction "AREF_42") (pintype "bidirectional"))
      (node (ref "IC5") (pin "44") (pinfunction "AVCC_44") (pintype "bidirectional"))
      (node (ref "Q1") (pin "2") (pinfunction "E_2") (pintype "passive"))
      (node (ref "Q2") (pin "2") (pinfunction "E_2") (pintype "passive"))
      (node (ref "Q3") (pin "2") (pinfunction "E_2") (pintype "passive"))
      (node (ref "Q4") (pin "2") (pinfunction "E_2") (pintype "passive"))
      (node (ref "Q5") (pin "2") (pinfunction "E_2") (pintype "passive"))
      (node (ref "Q6") (pin "2") (pinfunction "E_2") (pintype "passive"))
      (node (ref "Q7") (pin "2") (pinfunction "E_2") (pintype "passive"))
      (node (ref "R2") (pin "1") (pinfunction "1_1") (pintype "passive"))
      (node (ref "R5") (pin "2") (pinfunction "2_2") (pintype "passive"))
      (node (ref "R9") (pin "2") (pinfunction "2_2") (pintype "passive"))
      (node (ref "TP_VCC") (pin "TP") (pinfunction "TP_TP") (pintype "input"))
      (node (ref "U1") (pin "5") (pinfunction "OUT_5") (pintype "passive"))
    )
    (net (code "63") (name "V_BATT") (class "Default")
      (node (ref "BAT+") (pin "TP") (pinfunction "TP_TP") (pintype "input"))
      (node (ref "C10") (pin "1") (pinfunction "1_1") (pintype "passive"))
      (node (ref "C12") (pin "+") (pinfunction "+_+") (pintype "passive"))
      (node (ref "C9") (pin "+") (pinfunction "+_+") (pintype "passive"))
      (node (ref "IC6") (pin "4") (pinfunction "VIN_4") (pintype "power_in"))
      (node (ref "R15") (pin "1") (pinfunction "1_1") (pintype "passive"))
      (node (ref "U1") (pin "1") (pinfunction "IN_1") (pintype "input"))
      (node (ref "U2") (pin "3") (pinfunction "VBAT_3") (pintype "power_in"))
    )
    (net (code "64") (name "unconnected-(HM11-PadNC1)") (class "Default")
      (node (ref "HM11") (pin "NC1") (pinfunction "NC1_NC1") (pintype "bidirectional"))
    )
    (net (code "65") (name "unconnected-(HM11-PadNC2)") (class "Default")
      (node (ref "HM11") (pin "NC2") (pinfunction "NC2_NC2") (pintype "bidirectional"))
    )
    (net (code "66") (name "unconnected-(HM11-PadNC3)") (class "Default")
      (node (ref "HM11") (pin "NC3") (pinfunction "NC3_NC3") (pintype "bidirectional"))
    )
    (net (code "67") (name "unconnected-(HM11-PadNV1)") (class "Default")
      (node (ref "HM11") (pin "NV1") (pinfunction "NV1_NV1") (pintype "bidirectional"))
    )
    (net (code "68") (name "unconnected-(HM11-PadNV2)") (class "Default")
      (node (ref "HM11") (pin "NV2") (pinfunction "NV2_NV2") (pintype "bidirectional"))
    )
    (net (code "69") (name "unconnected-(HM11-PadPIO0)") (class "Default")
      (node (ref "HM11") (pin "PIO0") (pinfunction "PIO0_PIO0") (pintype "bidirectional"))
    )
    (net (code "70") (name "unconnected-(HM11-PadPIO2)") (class "Default")
      (node (ref "HM11") (pin "PIO2") (pinfunction "PIO2_PIO2") (pintype "bidirectional"))
    )
    (net (code "71") (name "unconnected-(HM11-PadPIO3)") (class "Default")
      (node (ref "HM11") (pin "PIO3") (pinfunction "PIO3_PIO3") (pintype "bidirectional"))
    )
    (net (code "72") (name "unconnected-(IC1-DRDY-Pad15)") (class "Default")
      (node (ref "IC1") (pin "15") (pinfunction "DRDY_15") (pintype "bidirectional"))
    )
    (net (code "73") (name "unconnected-(IC1-NC-Pad3)") (class "Default")
      (node (ref "IC1") (pin "3") (pinfunction "NC_3") (pintype "bidirectional"))
    )
    (net (code "74") (name "unconnected-(IC1-NC-Pad5)") (class "Default")
      (node (ref "IC1") (pin "5") (pinfunction "NC_5") (pintype "bidirectional"))
    )
    (net (code "75") (name "unconnected-(IC1-NC-Pad6)") (class "Default")
      (node (ref "IC1") (pin "6") (pinfunction "NC_6") (pintype "bidirectional"))
    )
    (net (code "76") (name "unconnected-(IC1-NC-Pad7)") (class "Default")
      (node (ref "IC1") (pin "7") (pinfunction "NC_7") (pintype "bidirectional"))
    )
    (net (code "77") (name "unconnected-(IC1-NC-Pad14)") (class "Default")
      (node (ref "IC1") (pin "14") (pinfunction "NC_14") (pintype "bidirectional"))
    )
    (net (code "78") (name "unconnected-(IC2-OUT7-Pad12)") (class "Default")
      (node (ref "IC2") (pin "12") (pinfunction "OUT7_12") (pintype "bidirectional"))
    )
    (net (code "79") (name "unconnected-(IC2-OUT15-Pad20)") (class "Default")
      (node (ref "IC2") (pin "20") (pinfunction "OUT15_20") (pintype "bidirectional"))
    )
    (net (code "80") (name "unconnected-(IC2-SDO-Pad22)") (class "Default")
      (node (ref "IC2") (pin "22") (pinfunction "SDO_22") (pintype "bidirectional"))
    )
    (net (code "81") (name "unconnected-(IC5-PB5(ADC12)-Pad29)") (class "Default")
      (node (ref "IC5") (pin "29") (pinfunction "PB5(ADC12)_29") (pintype "bidirectional"))
    )
    (net (code "82") (name "unconnected-(IC5-PB6(ADC13)-Pad30)") (class "Default")
      (node (ref "IC5") (pin "30") (pinfunction "PB6(ADC13)_30") (pintype "bidirectional"))
    )
    (net (code "83") (name "unconnected-(IC5-PC6-Pad31)") (class "Default")
      (node (ref "IC5") (pin "31") (pinfunction "PC6_31") (pintype "bidirectional"))
    )
    (net (code "84") (name "unconnected-(IC5-PD4(ADC8)-Pad25)") (class "Default")
      (node (ref "IC5") (pin "25") (pinfunction "PD4(ADC8)_25") (pintype "bidirectional"))
    )
    (net (code "85") (name "unconnected-(IC5-PD7(ADC10)-Pad27)") (class "Default")
      (node (ref "IC5") (pin "27") (pinfunction "PD7(ADC10)_27") (pintype "bidirectional"))
    )
    (net (code "86") (name "unconnected-(IC5-PE2{slash}~{HWB}-Pad33)") (class "Default")
      (node (ref "IC5") (pin "33") (pinfunction "PE2/~{HWB}_33") (pintype "bidirectional"))
    )
    (net (code "87") (name "unconnected-(IC5-PE6-Pad1)") (class "Default")
      (node (ref "IC5") (pin "1") (pinfunction "PE6_1") (pintype "bidirectional"))
    )
    (net (code "88") (name "unconnected-(IC5-PF0(ADC0)-Pad41)") (class "Default")
      (node (ref "IC5") (pin "41") (pinfunction "PF0(ADC0)_41") (pintype "bidirectional"))
    )
    (net (code "89") (name "unconnected-(IC5-PF1(ADC1)-Pad40)") (class "Default")
      (node (ref "IC5") (pin "40") (pinfunction "PF1(ADC1)_40") (pintype "bidirectional"))
    )
    (net (code "90") (name "unconnected-(IC5-PF4(ADC4)-Pad39)") (class "Default")
      (node (ref "IC5") (pin "39") (pinfunction "PF4(ADC4)_39") (pintype "bidirectional"))
    )
    (net (code "91") (name "unconnected-(IC5-PF5(ADC5)-Pad38)") (class "Default")
      (node (ref "IC5") (pin "38") (pinfunction "PF5(ADC5)_38") (pintype "bidirectional"))
    )
    (net (code "92") (name "unconnected-(IC5-PF6(ADC6)-Pad37)") (class "Default")
      (node (ref "IC5") (pin "37") (pinfunction "PF6(ADC6)_37") (pintype "bidirectional"))
    )
    (net (code "93") (name "unconnected-(IC5-PF7(ADC7)-Pad36)") (class "Default")
      (node (ref "IC5") (pin "36") (pinfunction "PF7(ADC7)_36") (pintype "bidirectional"))
    )
    (net (code "94") (name "unconnected-(IC6-OFFT-Pad6)") (class "Default")
      (node (ref "IC6") (pin "6") (pinfunction "OFFT_6") (pintype "input"))
    )
    (net (code "95") (name "unconnected-(IC6-ONT-Pad2)") (class "Default")
      (node (ref "IC6") (pin "2") (pinfunction "ONT_2") (pintype "input"))
    )
    (net (code "96") (name "unconnected-(J1-ID-Pad4)") (class "Default")
      (node (ref "J1") (pin "4") (pinfunction "ID_4") (pintype "bidirectional"))
    )
    (net (code "97") (name "unconnected-(SW1-Pad3)") (class "Default")
      (node (ref "SW1") (pin "3") (pinfunction "3_3") (pintype "bidirectional"))
    )
    (net (code "98") (name "unconnected-(SW1-Pad4)") (class "Default")
      (node (ref "SW1") (pin "4") (pinfunction "4_4") (pintype "bidirectional"))
    )
  )
)
